# design.net
KiCad netlist of a schematic drawn in Altium Designer
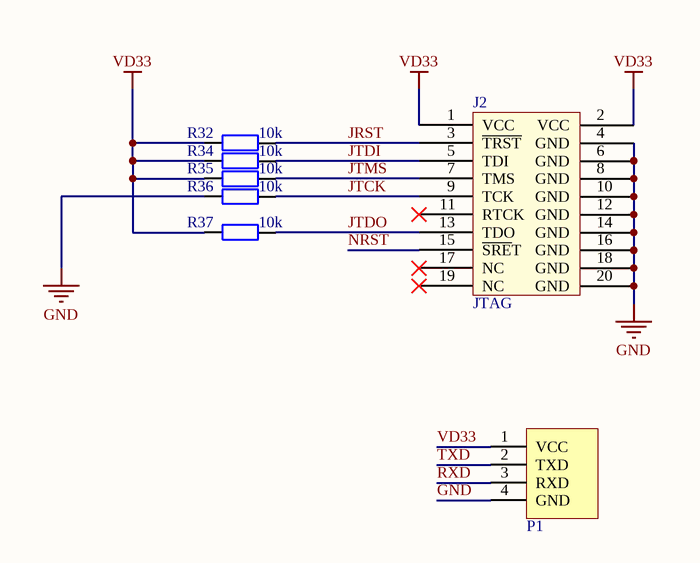
[diagram p0: 下载&调试.SchDoc]

(export (version "E")
  (design (tool "Eeschema 10.0.6"))
  (components
    (comp (ref "J2")
      (value "JTAG")
      (footprint "JTAG_20")
      (description "2*10Pin,Jtag����")
      (libsource (lib "ECG") (part "JTAG"))
    )
    (comp (ref "P1") (value "UART") (footprint "�������ؽӿ�") (libsource (lib "ECG") (part "UART")))
    (comp (ref "R32")
      (value "10k")
      (footprint "LC-0805_R")
      (description "10k��,0805,��5%")
      (libsource (lib "ECG") (part "R"))
    )
    (comp (ref "R34")
      (value "10k")
      (footprint "LC-0805_R")
      (description "10k��,0805,��5%")
      (libsource (lib "ECG") (part "R"))
    )
    (comp (ref "R35")
      (value "10k")
      (footprint "LC-0805_R")
      (description "10k��,0805,��5%")
      (libsource (lib "ECG") (part "R"))
    )
    (comp (ref "R36")
      (value "10k")
      (footprint "LC-0805_R")
      (description "10k��,0805,��5%")
      (libsource (lib "ECG") (part "R"))
    )
    (comp (ref "R37")
      (value "10k")
      (footprint "LC-0805_R")
      (description "10k��,0805,��5%")
      (libsource (lib "ECG") (part "R"))
    )
  )
  (nets
    (net (code "1") (name "/JRST") (class "Default")
      (node (ref "J2") (pin "3") (pinfunction "~{TRST}_3") (pintype "open_collector"))
      (node (ref "R32") (pin "2") (pintype "passive"))
    )
    (net (code "2") (name "/JTCK") (class "Default")
      (node (ref "J2") (pin "9") (pinfunction "TCK_9") (pintype "open_collector"))
      (node (ref "R36") (pin "2") (pintype "passive"))
    )
    (net (code "3") (name "/JTDI") (class "Default")
      (node (ref "J2") (pin "5") (pinfunction "TDI_5") (pintype "open_collector"))
      (node (ref "R34") (pin "2") (pintype "passive"))
    )
    (net (code "4") (name "/JTDO") (class "Default")
      (node (ref "J2") (pin "13") (pinfunction "TDO_13") (pintype "open_collector"))
      (node (ref "R37") (pin "2") (pintype "passive"))
    )
    (net (code "5") (name "/JTMS") (class "Default")
      (node (ref "J2") (pin "7") (pinfunction "TMS_7") (pintype "open_collector"))
      (node (ref "R35") (pin "2") (pintype "passive"))
    )
    (net (code "6") (name "/NRST") (class "Default")
      (node (ref "J2") (pin "15") (pinfunction "~{SRE}T_15") (pintype "open_collector"))
    )
    (net (code "7") (name "/RXD") (class "Default")
      (node (ref "P1") (pin "3") (pinfunction "RXD_3") (pintype "passive"))
    )
    (net (code "8") (name "/TXD") (class "Default")
      (node (ref "P1") (pin "2") (pinfunction "TXD_2") (pintype "passive"))
    )
    (net (code "9") (name "GND") (class "Default")
      (node (ref "J2") (pin "10") (pinfunction "GND_10") (pintype "open_collector"))
      (node (ref "J2") (pin "12") (pinfunction "GND_12") (pintype "open_collector"))
      (node (ref "J2") (pin "14") (pinfunction "GND_14") (pintype "open_collector"))
      (node (ref "J2") (pin "16") (pinfunction "GND_16") (pintype "open_collector"))
      (node (ref "J2") (pin "18") (pinfunction "GND_18") (pintype "open_collector"))
      (node (ref "J2") (pin "20") (pinfunction "GND_20") (pintype "open_collector"))
      (node (ref "J2") (pin "4") (pinfunction "GND_4") (pintype "open_collector"))
      (node (ref "J2") (pin "6") (pinfunction "GND_6") (pintype "open_collector"))
      (node (ref "J2") (pin "8") (pinfunction "GND_8") (pintype "open_collector"))
      (node (ref "P1") (pin "4") (pinfunction "GND_4") (pintype "passive"))
      (node (ref "R36") (pin "1") (pintype "passive"))
    )
    (net (code "10") (name "VD33") (class "Default")
      (node (ref "J2") (pin "1") (pinfunction "VCC_1") (pintype "open_collector"))
      (node (ref "J2") (pin "2") (pinfunction "VCC_2") (pintype "open_collector"))
      (node (ref "P1") (pin "1") (pinfunction "VCC_1") (pintype "passive"))
      (node (ref "R32") (pin "1") (pintype "passive"))
      (node (ref "R34") (pin "1") (pintype "passive"))
      (node (ref "R35") (pin "1") (pintype "passive"))
      (node (ref "R37") (pin "1") (pintype "passive"))
    )
    (net (code "11") (name "unconnected-(J2-NC-Pad17)") (class "Default")
      (node (ref "J2") (pin "17") (pinfunction "NC_17") (pintype "open_collector+no_connect"))
    )
    (net (code "12") (name "unconnected-(J2-NC-Pad19)") (class "Default")
      (node (ref "J2") (pin "19") (pinfunction "NC_19") (pintype "open_collector+no_connect"))
    )
    (net (code "13") (name "unconnected-(J2-RTCK-Pad11)") (class "Default")
      (node (ref "J2") (pin "11") (pinfunction "RTCK_11") (pintype "open_collector+no_connect"))
    )
  )
)
